# PULSE.net
KiCad netlist of a schematic drawn in Altium Designer
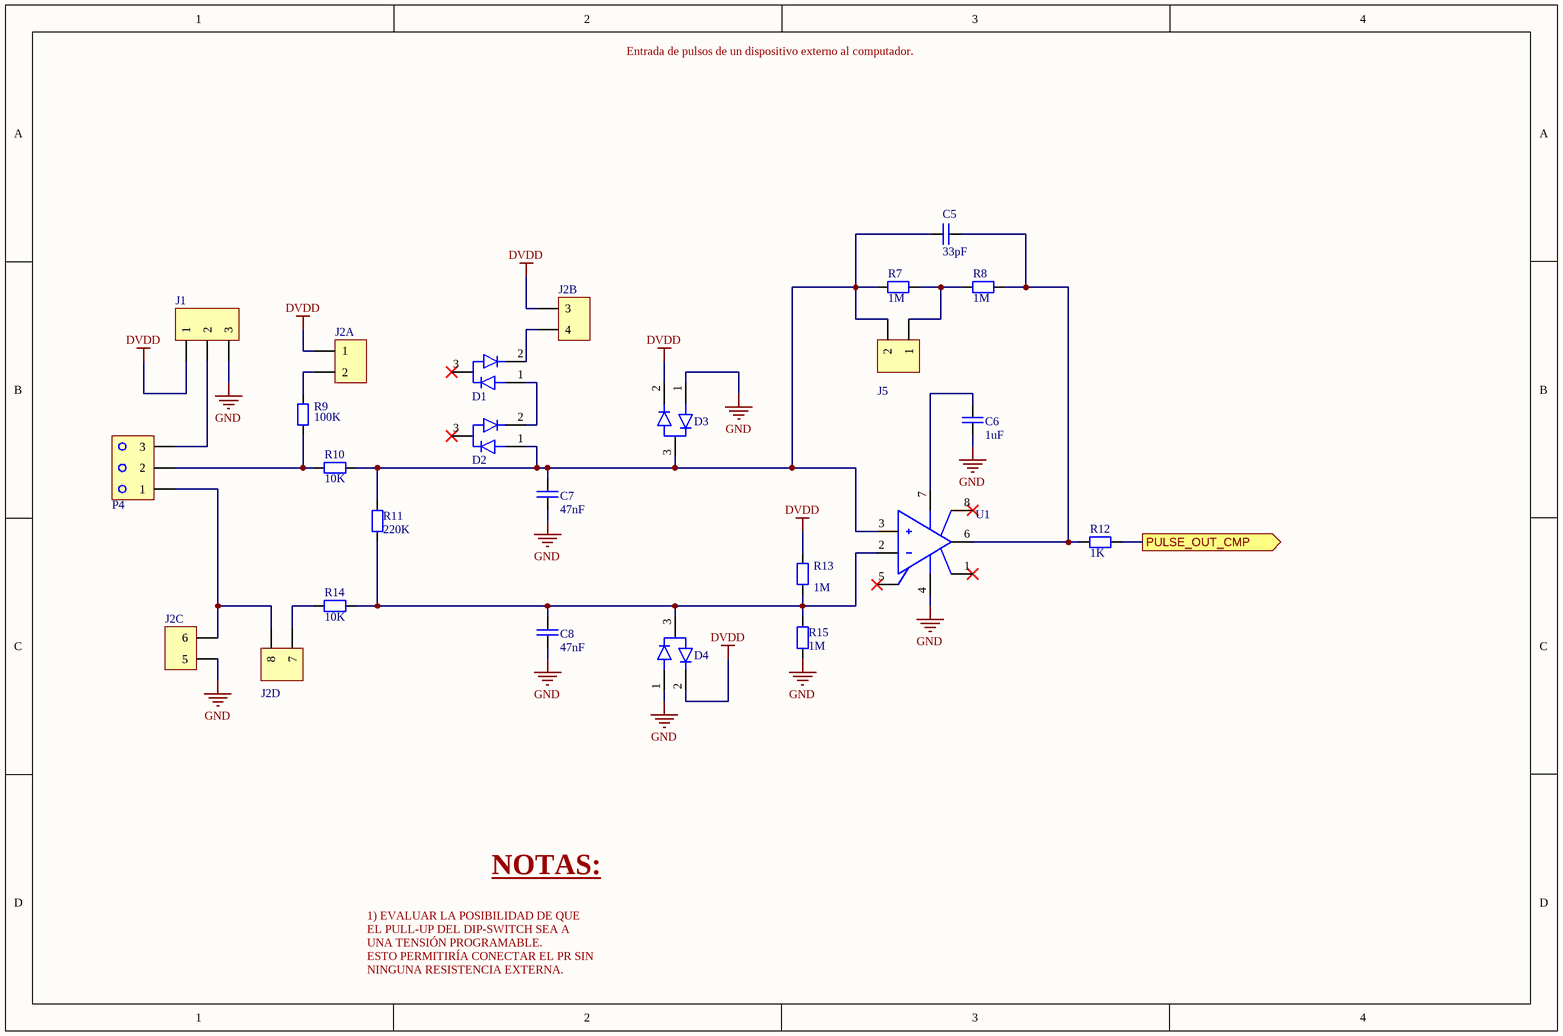
[diagram p0: PULSE.SchDoc]

(export (version "E")
  (design (tool "Eeschema 10.0.6"))
  (components
    (comp (ref "C5")
      (value "33pF")
      (footprint "CAP_SM0805_YAGEOCC2_N")
      (description "CAP 33pF SM0805 NPO 50V YAGEO CC2")
      (fields
        (field (name "MANUFACTURER") "Yageo")
        (field (name "MANUFACTURER PART NUMBER") "CC0805JRNPO9BN330")
      )
      (libsource (lib "Yageo") (part "CC0805JRNPO9BN330"))
    )
    (comp (ref "C6")
      (value "1uF")
      (footprint "CAP_SM0805_YAGEOCC2_N")
      (description "CAP 1uF SM0805 X7R 25V YAGEO CC2")
      (fields
        (field (name "MANUFACTURER") "Yageo")
        (field (name "MANUFACTURER PART NUMBER") "CC0805KKX7R8BB105")
      )
      (libsource (lib "Yageo") (part "CC0805KKX7R8BB105"))
    )
    (comp (ref "C7")
      (value "47nF")
      (footprint "CAP_SM0805_YAGEOCC2_N")
      (description "CAP 47nF SM0805 X7R 25V YAGEO CC2")
      (fields
        (field (name "MANUFACTURER") "Yageo")
        (field (name "MANUFACTURER PART NUMBER") "CC0805KRX7R8BB473")
      )
      (libsource (lib "Yageo") (part "CC0805KRX7R8BB473"))
    )
    (comp (ref "C8")
      (value "47nF")
      (footprint "CAP_SM0805_YAGEOCC2_N")
      (description "CAP 47nF SM0805 X7R 25V YAGEO CC2")
      (fields
        (field (name "MANUFACTURER") "Yageo")
        (field (name "MANUFACTURER PART NUMBER") "CC0805KRX7R8BB473")
      )
      (libsource (lib "Yageo") (part "CC0805KRX7R8BB473"))
    )
    (comp (ref "D1")
      (value "BAV23S")
      (footprint "BAV23S")
      (description "DIODE ARRAY GP 250V 200MA SOT23")
      (fields (field (name "MANUFACTURER") "onsemi"))
      (libsource (lib "diode") (part "BAV23S"))
    )
    (comp (ref "D2")
      (value "BAV23S")
      (footprint "BAV23S")
      (description "DIODE ARRAY GP 250V 200MA SOT23")
      (fields (field (name "MANUFACTURER") "onsemi"))
      (libsource (lib "diode") (part "BAV23S"))
    )
    (comp (ref "D3")
      (value "BAV23S")
      (footprint "BAV23S")
      (description "DIODE ARRAY GP 250V 200MA SOT23")
      (fields (field (name "MANUFACTURER") "onsemi"))
      (libsource (lib "diode") (part "BAV23S"))
    )
    (comp (ref "D4")
      (value "BAV23S")
      (footprint "BAV23S")
      (description "DIODE ARRAY GP 250V 200MA SOT23")
      (fields (field (name "MANUFACTURER") "onsemi"))
      (libsource (lib "diode") (part "BAV23S"))
    )
    (comp (ref "J1")
      (value "~")
      (footprint "HEADER PIN 1X3")
      (description "1 x 3 - Cuttable - true hole  2.54mm - Pb free")
      (fields
        (field (name "MANUFACTURER") "Amphenol ICC")
        (field (name "MANUFACTURER PART NUMBER") "54101-T06-00")
      )
      (libsource (lib "header_pin") (part "54101-T0600LF-03"))
    )
    (comp (ref "J2")
      (value "Usar equivalente")
      (footprint "HEADER PIN 2X4")
      (description "2 x 4  - true hole  2.54mm")
      (fields
        (field (name "MANUFACTURER") "Amphenol ICC")
        (field (name "MANUFACTURER PARTNUMBER") "54102-T0604LF")
      )
      (libsource (lib "") (part "54102-T0604LF-JUMPER_2"))
    )
    (comp (ref "J5")
      (value "Usar Equivalente")
      (footprint "HEADER PIN 1X2")
      (description "1 x 2 - true hole  2.54mm - Pb free")
      (fields
        (field (name "MANUFACTURER") "Amphenol ICC")
        (field (name "MANUFACTURER PART NUMBER") "54101-T0602LF")
      )
      (libsource (lib "header_pin") (part "54101-T0602LF"))
    )
    (comp (ref "P4")
      (value "WJ15EDGVC-3.81-3P")
      (footprint "HEADER PLUG 3")
      (description "TERM BLOK FEMALE 1X3 3.81MM")
      (fields (field (name "MANUFACTURER") "Ningbo Kangnex Elec"))
      (libsource (lib "plug") (part "WJ15EDGVC-3.81-3P"))
    )
    (comp (ref "R7")
      (value "1M")
      (footprint "RES_SM0805_YAGEORC_N")
      (description "RES 1M SM0805 YAGEO RC_L")
      (fields
        (field (name "MANUFACTURER") "Yageo")
        (field (name "MANUFACTURER PART NUMBER") "RC0805FR-071ML")
      )
      (libsource (lib "Yageo") (part "RC0805FR-071ML"))
    )
    (comp (ref "R8")
      (value "1M")
      (footprint "RES_SM0805_YAGEORC_N")
      (description "RES 1M SM0805 YAGEO RC_L")
      (fields
        (field (name "MANUFACTURER") "Yageo")
        (field (name "MANUFACTURER PART NUMBER") "RC0805FR-071ML")
      )
      (libsource (lib "Yageo") (part "RC0805FR-071ML"))
    )
    (comp (ref "R9")
      (value "100K")
      (footprint "RES_SM0805_YAGEORC_N")
      (description "RES 100K SM0805 YAGEO RC_L")
      (fields
        (field (name "MANUFACTURER") "Yageo")
        (field (name "MANUFACTURER PART NUMBER") "RC0805FR-07100KL")
      )
      (libsource (lib "Yageo") (part "RC0805FR-07100KL"))
    )
    (comp (ref "R10")
      (value "10K")
      (footprint "RES_SM0805_YAGEORC_N")
      (description "RES 10K SM0805 YAGEO RC_L")
      (fields
        (field (name "MANUFACTURER") "Yageo")
        (field (name "MANUFACTURER PART NUMBER") "RC0805FR-0710KL")
      )
      (libsource (lib "Yageo") (part "RC0805FR-0710KL"))
    )
    (comp (ref "R11")
      (value "220K")
      (footprint "RES_SM0805_YAGEORC_N")
      (description "RES 220K SM0805 YAGEO RC_L")
      (fields
        (field (name "MANUFACTURER") "Yageo")
        (field (name "MANUFACTURER PART NUMBER") "RC0805FR-07220KL")
      )
      (libsource (lib "Yageo") (part "RC0805FR-07220KL"))
    )
    (comp (ref "R12")
      (value "1K")
      (footprint "RES_SM0805_YAGEORC_N")
      (description "RES 1K SM0805 YAGEO RC_L")
      (fields
        (field (name "MANUFACTURER") "Yageo")
        (field (name "MANUFACTURER PART NUMBER") "RC0805FR-071KL")
      )
      (libsource (lib "Yageo") (part "RC0805FR-071KL"))
    )
    (comp (ref "R13")
      (value "1M")
      (footprint "RES_SM0805_YAGEORC_N")
      (description "RES 1M SM0805 YAGEO RC_L")
      (fields
        (field (name "MANUFACTURER") "Yageo")
        (field (name "MANUFACTURER PART NUMBER") "RC0805FR-071ML")
      )
      (libsource (lib "") (part "RC0805FR-071ML_1"))
    )
    (comp (ref "R14")
      (value "10K")
      (footprint "RES_SM0805_YAGEORC_N")
      (description "RES 10K SM0805 YAGEO RC_L")
      (fields
        (field (name "MANUFACTURER") "Yageo")
        (field (name "MANUFACTURER PART NUMBER") "RC0805FR-0710KL")
      )
      (libsource (lib "Yageo") (part "RC0805FR-0710KL"))
    )
    (comp (ref "R15")
      (value "1M")
      (footprint "RES_SM0805_YAGEORC_N")
      (description "RES 1M SM0805 YAGEO RC_L")
      (fields
        (field (name "MANUFACTURER") "Yageo")
        (field (name "MANUFACTURER PART NUMBER") "RC0805FR-071ML")
      )
      (libsource (lib "") (part "RC0805FR-071ML_1"))
    )
    (comp (ref "U1")
      (value "MCP6541")
      (footprint "MCP6541-E/SN")
      (description "IC COMP PP I/O SNGL 1.6V 8SOIC")
      (fields
        (field (name "MANUFACTURER") "Microchip Tech")
        (field (name "MANUFACTURER PART NUMBER") "MCP6541-E/SN")
      )
      (libsource (lib "OP_Amps") (part "MCP6541-E/SN"))
    )
  )
  (nets
    (net (code "1") (name "/PULSE_OUT_CMP") (class "Default")
      (node (ref "R12") (pin "2") (pintype "passive"))
    )
    (net (code "2") (name "DVDD") (class "Default")
      (node (ref "D3") (pin "2") (pinfunction "2_2") (pintype "passive"))
      (node (ref "D4") (pin "2") (pinfunction "2_2") (pintype "passive"))
      (node (ref "J1") (pin "1") (pinfunction "1_1") (pintype "passive"))
      (node (ref "J2") (pin "1") (pinfunction "1_1") (pintype "passive"))
      (node (ref "J2") (pin "3") (pinfunction "3_3") (pintype "passive"))
      (node (ref "R13") (pin "2") (pintype "passive"))
    )
    (net (code "3") (name "GND") (class "Default")
      (node (ref "C6") (pin "2") (pintype "passive"))
      (node (ref "C7") (pin "2") (pintype "passive"))
      (node (ref "C8") (pin "2") (pintype "passive"))
      (node (ref "D3") (pin "1") (pinfunction "1_1") (pintype "passive"))
      (node (ref "D4") (pin "1") (pinfunction "1_1") (pintype "passive"))
      (node (ref "J1") (pin "3") (pinfunction "3_3") (pintype "passive"))
      (node (ref "J2") (pin "5") (pinfunction "5_5") (pintype "passive"))
      (node (ref "R15") (pin "1") (pintype "passive"))
      (node (ref "U1") (pin "4") (pinfunction "V-_4") (pintype "power_in"))
    )
    (net (code "4") (name "Net-(D1-Pad1)") (class "Default")
      (node (ref "D1") (pin "1") (pinfunction "1_1") (pintype "passive"))
      (node (ref "D2") (pin "2") (pinfunction "2_2") (pintype "passive"))
    )
    (net (code "5") (name "Net-(D1-Pad2)") (class "Default")
      (node (ref "D1") (pin "2") (pinfunction "2_2") (pintype "passive"))
      (node (ref "J2") (pin "4") (pinfunction "4_4") (pintype "passive"))
    )
    (net (code "6") (name "Net-(J1-Pad2)") (class "Default")
      (node (ref "J1") (pin "2") (pinfunction "2_2") (pintype "passive"))
      (node (ref "P4") (pin "3") (pinfunction "3_3") (pintype "passive"))
    )
    (net (code "7") (name "Net-(J2-Pad2)") (class "Default")
      (node (ref "J2") (pin "2") (pinfunction "2_2") (pintype "passive"))
      (node (ref "R9") (pin "2") (pintype "passive"))
    )
    (net (code "8") (name "Net-(J2-Pad6)") (class "Default")
      (node (ref "J2") (pin "6") (pinfunction "6_6") (pintype "passive"))
      (node (ref "J2") (pin "8") (pinfunction "8_8") (pintype "passive"))
      (node (ref "P4") (pin "1") (pinfunction "1_1") (pintype "passive"))
    )
    (net (code "9") (name "Net-(J2-Pad7)") (class "Default")
      (node (ref "J2") (pin "7") (pinfunction "7_7") (pintype "passive"))
      (node (ref "R14") (pin "1") (pintype "passive"))
    )
    (net (code "10") (name "Net-(J5-Pad1)") (class "Default")
      (node (ref "J5") (pin "1") (pinfunction "1_1") (pintype "passive"))
      (node (ref "R7") (pin "2") (pintype "passive"))
      (node (ref "R8") (pin "1") (pintype "passive"))
    )
    (net (code "11") (name "Net-(P4-Pad2)") (class "Default")
      (node (ref "P4") (pin "2") (pinfunction "2_2") (pintype "passive"))
      (node (ref "R10") (pin "1") (pintype "passive"))
      (node (ref "R9") (pin "1") (pintype "passive"))
    )
    (net (code "12") (name "Net-(U1-IN+)") (class "Default")
      (node (ref "C5") (pin "1") (pintype "passive"))
      (node (ref "C7") (pin "1") (pintype "passive"))
      (node (ref "D2") (pin "1") (pinfunction "1_1") (pintype "passive"))
      (node (ref "D3") (pin "3") (pinfunction "3_3") (pintype "passive"))
      (node (ref "J5") (pin "2") (pinfunction "2_2") (pintype "passive"))
      (node (ref "R10") (pin "2") (pintype "passive"))
      (node (ref "R11") (pin "2") (pintype "passive"))
      (node (ref "R7") (pin "1") (pintype "passive"))
      (node (ref "U1") (pin "3") (pinfunction "IN+_3") (pintype "passive"))
    )
    (net (code "13") (name "Net-(U1-IN-)") (class "Default")
      (node (ref "C8") (pin "1") (pintype "passive"))
      (node (ref "D4") (pin "3") (pinfunction "3_3") (pintype "passive"))
      (node (ref "R11") (pin "1") (pintype "passive"))
      (node (ref "R13") (pin "1") (pintype "passive"))
      (node (ref "R14") (pin "2") (pintype "passive"))
      (node (ref "R15") (pin "2") (pintype "passive"))
      (node (ref "U1") (pin "2") (pinfunction "IN-_2") (pintype "passive"))
    )
    (net (code "14") (name "Net-(U1-OUT)") (class "Default")
      (node (ref "C5") (pin "2") (pintype "passive"))
      (node (ref "R12") (pin "1") (pintype "passive"))
      (node (ref "R8") (pin "2") (pintype "passive"))
      (node (ref "U1") (pin "6") (pinfunction "OUT_6") (pintype "passive"))
    )
    (net (code "15") (name "Net-(U1-V+)") (class "Default")
      (node (ref "C6") (pin "1") (pintype "passive"))
      (node (ref "U1") (pin "7") (pinfunction "V+_7") (pintype "power_in"))
    )
    (net (code "16") (name "unconnected-(D1-Pad3)") (class "Default")
      (node (ref "D1") (pin "3") (pinfunction "3_3") (pintype "passive+no_connect"))
    )
    (net (code "17") (name "unconnected-(D2-Pad3)") (class "Default")
      (node (ref "D2") (pin "3") (pinfunction "3_3") (pintype "passive+no_connect"))
    )
    (net (code "18") (name "unconnected-(U1-OS_NUL-Pad1)") (class "Default")
      (node (ref "U1") (pin "1") (pinfunction "OS_NUL_1") (pintype "passive+no_connect"))
    )
    (net (code "19") (name "unconnected-(U1-OS_NUL-Pad5)") (class "Default")
      (node (ref "U1") (pin "5") (pinfunction "OS_NUL_5") (pintype "passive+no_connect"))
    )
    (net (code "20") (name "unconnected-(U1-TAB-Pad8)") (class "Default")
      (node (ref "U1") (pin "8") (pinfunction "TAB_8") (pintype "passive+no_connect"))
    )
  )
)
